# PCB_Cubesat_4L_-_Revision_History.net
KiCad netlist of a schematic drawn in Altium Designer
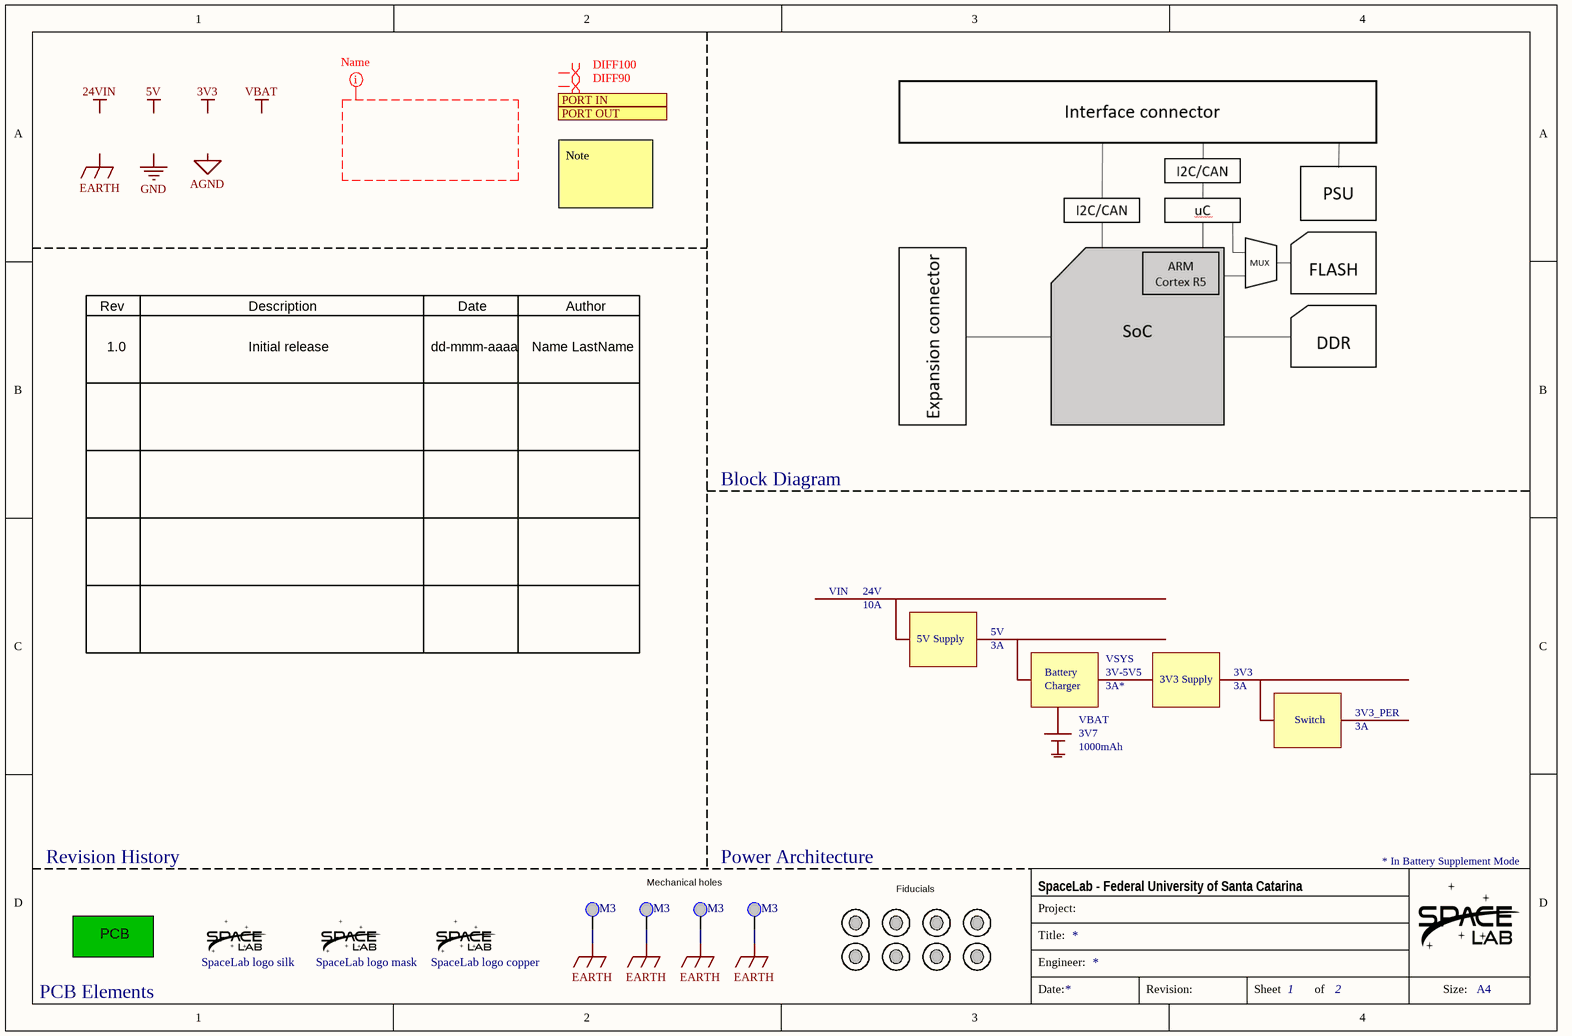
[diagram p0: _PCB_Cubesat_4L - Revision History.SchDoc]

(export (version "E")
  (design (tool "Eeschema 10.0.6"))
  (components
    (comp (ref "COP1")
      (value "SpaceLab logo copper")
      (footprint "SpaceLab logo copper")
      (description "SpaceLab logo on copper layer")
      (libsource (lib "Miscellaneous") (part "SpaceLab logo copper"))
    )
    (comp (ref "FD1")
      (value "Fiducial 1.3")
      (footprint "Fiducial 1.3mm")
      (description "Fiducial 1.3mm")
      (libsource (lib "Miscelaneos") (part "Fiducial 1.3"))
    )
    (comp (ref "FD2")
      (value "Fiducial 1.3")
      (footprint "Fiducial 1.3mm")
      (description "Fiducial 1.3mm")
      (libsource (lib "Miscelaneos") (part "Fiducial 1.3"))
    )
    (comp (ref "FD3")
      (value "Fiducial 1.3")
      (footprint "Fiducial 1.3mm")
      (description "Fiducial 1.3mm")
      (libsource (lib "Miscelaneos") (part "Fiducial 1.3"))
    )
    (comp (ref "FD4")
      (value "Fiducial 1.3")
      (footprint "Fiducial 1.3mm")
      (description "Fiducial 1.3mm")
      (libsource (lib "Miscelaneos") (part "Fiducial 1.3"))
    )
    (comp (ref "FD5")
      (value "Fiducial 1.3")
      (footprint "Fiducial 1.3mm")
      (description "Fiducial 1.3mm")
      (libsource (lib "Miscelaneos") (part "Fiducial 1.3"))
    )
    (comp (ref "FD6")
      (value "Fiducial 1.3")
      (footprint "Fiducial 1.3mm")
      (description "Fiducial 1.3mm")
      (libsource (lib "Miscelaneos") (part "Fiducial 1.3"))
    )
    (comp (ref "FD7")
      (value "Fiducial 1.3")
      (footprint "Fiducial 1.3mm")
      (description "Fiducial 1.3mm")
      (libsource (lib "Miscelaneos") (part "Fiducial 1.3"))
    )
    (comp (ref "FD8")
      (value "Fiducial 1.3")
      (footprint "Fiducial 1.3mm")
      (description "Fiducial 1.3mm")
      (libsource (lib "Miscelaneos") (part "Fiducial 1.3"))
    )
    (comp (ref "MASK1")
      (value "SpaceLab logo mask")
      (footprint "SpaceLab logo mask")
      (description "SpaceLab logo on solder mask layer")
      (libsource (lib "Miscellaneous") (part "SpaceLab logo mask"))
    )
    (comp (ref "MEC1")
      (value "M3")
      (footprint "M3 hole")
      (description "M3 hole")
      (libsource (lib "Miscelaneos") (part "M3 hole"))
    )
    (comp (ref "MEC2")
      (value "M3")
      (footprint "M3 hole")
      (description "M3 hole")
      (libsource (lib "Miscelaneos") (part "M3 hole"))
    )
    (comp (ref "MEC3")
      (value "M3")
      (footprint "M3 hole")
      (description "M3 hole")
      (libsource (lib "Miscelaneos") (part "M3 hole"))
    )
    (comp (ref "MEC4")
      (value "M3")
      (footprint "M3 hole")
      (description "M3 hole")
      (libsource (lib "Miscelaneos") (part "M3 hole"))
    )
    (comp (ref "SILK1")
      (value "SpaceLab logo silk")
      (footprint "SpaceLab logo silk")
      (description "SpaceLab logo on silk screen layer")
      (libsource (lib "Miscellaneous") (part "SpaceLab logo silk"))
    )
    (comp (ref "_PCB1") (value "PCB spec") (description "PCB") (libsource (lib "Miscellaneous") (part "PCB")))
  )
  (nets
    (net (code "7") (name "EARTH") (class "Default")
      (node (ref "MEC1") (pin "0") (pinfunction "0_0") (pintype "passive"))
      (node (ref "MEC2") (pin "0") (pinfunction "0_0") (pintype "passive"))
      (node (ref "MEC3") (pin "0") (pinfunction "0_0") (pintype "passive"))
      (node (ref "MEC4") (pin "0") (pinfunction "0_0") (pintype "passive"))
    )
  )
)
